# makerbot.net
KiCad netlist of a schematic drawn in EAGLE
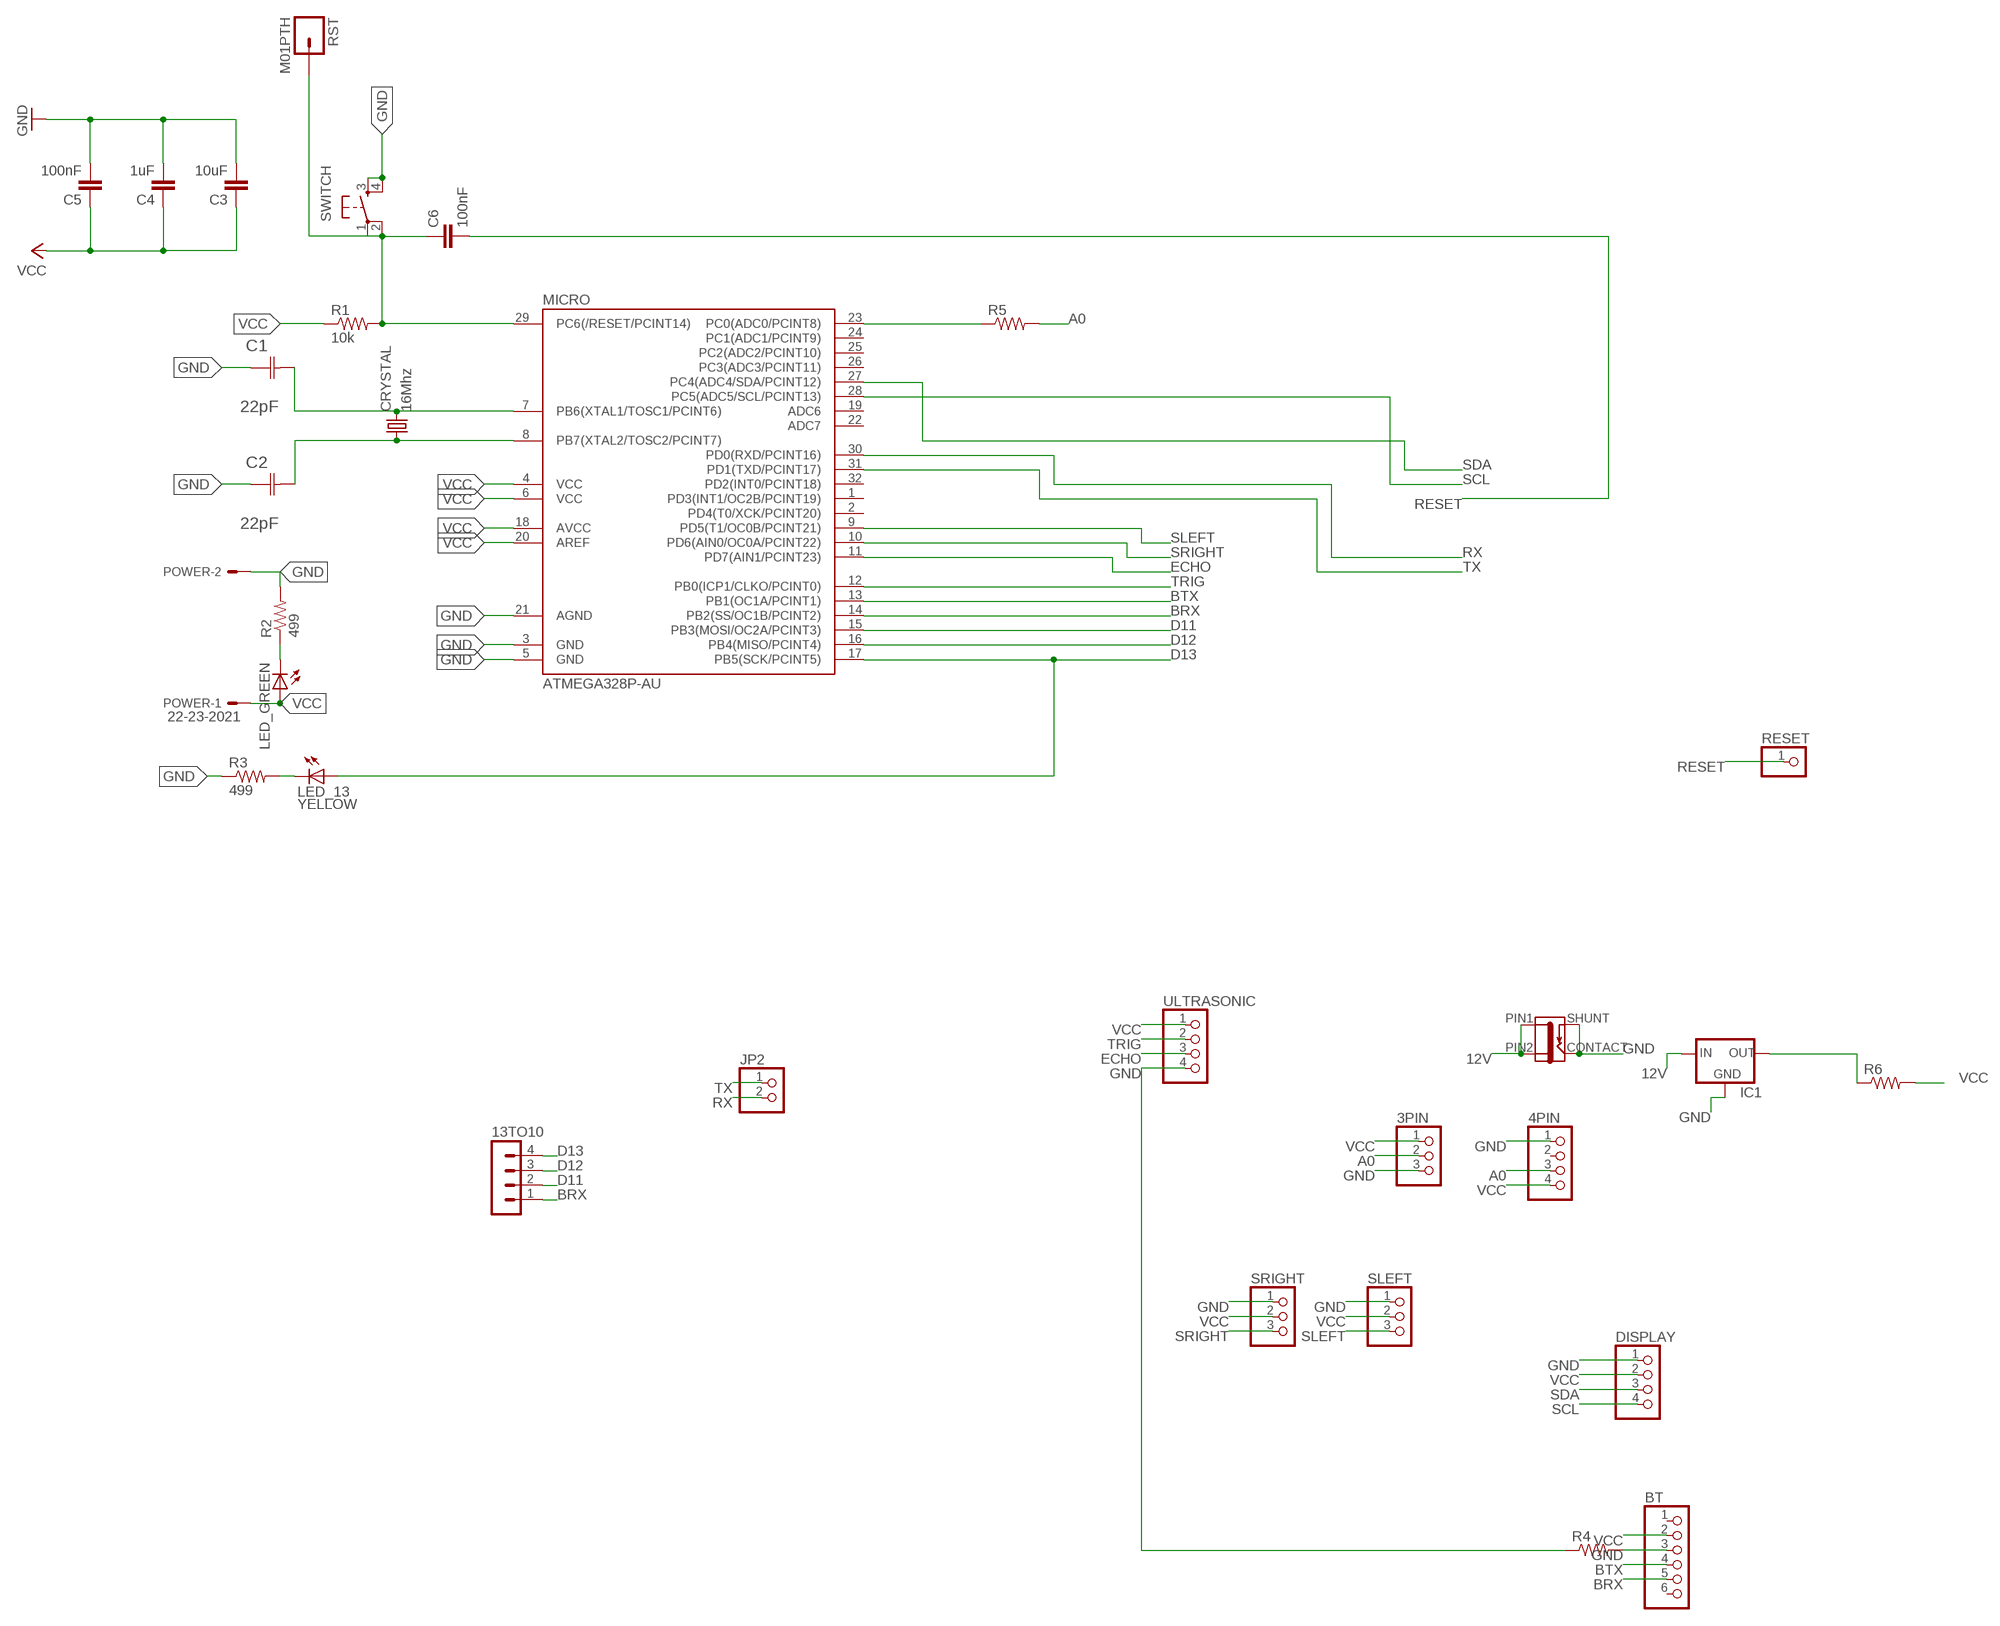
[diagram p0: schematic, sheet 1]

(export (version "E")
  (design (tool "Eeschema 10.0.6"))
  (components
    (comp (ref "3PIN")
      (value "PINHD-1X3")
      (footprint "eagle-import:1X03")
      (libsource (lib "eagle-import") (part "PINHD-1X3"))
    )
    (comp (ref "4PIN")
      (value "PINHD-1X4")
      (footprint "eagle-import:1X04")
      (libsource (lib "eagle-import") (part "PINHD-1X4"))
    )
    (comp (ref "13TO10")
      (value "MA04-1")
      (footprint "eagle-import:MA04-1")
      (libsource (lib "eagle-import") (part "MA04-1"))
    )
    (comp (ref "BT")
      (value "PINHD-1X6")
      (footprint "eagle-import:1X06")
      (libsource (lib "eagle-import") (part "PINHD-1X6"))
    )
    (comp (ref "C1")
      (value "22pF")
      (footprint "eagle-import:CAPC3216X178N")
      (fields (field (name "MPN") "0612ZC225MAT2A") (field (name "TOLERANCE") "±20%"))
      (libsource (lib "eagle-import") (part "0612ZC225MAT2A"))
    )
    (comp (ref "C2")
      (value "22pF")
      (footprint "eagle-import:CAPC3216X178N")
      (fields (field (name "MPN") "0612ZC225MAT2A") (field (name "TOLERANCE") "±20%"))
      (libsource (lib "eagle-import") (part "0612ZC225MAT2A"))
    )
    (comp (ref "C3")
      (value "10uF")
      (footprint "eagle-import:1206")
      (libsource (lib "eagle-import") (part "CAP1206"))
    )
    (comp (ref "C4")
      (value "1uF")
      (footprint "eagle-import:1206")
      (libsource (lib "eagle-import") (part "CAP1206"))
    )
    (comp (ref "C5")
      (value "100nF")
      (footprint "eagle-import:1206")
      (libsource (lib "eagle-import") (part "CAP1206"))
    )
    (comp (ref "C6")
      (value "100nF")
      (footprint "eagle-import:1206")
      (libsource (lib "eagle-import") (part "CAP1206"))
    )
    (comp (ref "CRYSTAL")
      (value "16Mhz")
      (footprint "eagle-import:CSM-7X-DU")
      (libsource (lib "eagle-import") (part "CSM-7X-DU"))
    )
    (comp (ref "DISPLAY")
      (value "PINHD-1X4")
      (footprint "eagle-import:1X04")
      (libsource (lib "eagle-import") (part "PINHD-1X4"))
    )
    (comp (ref "IC1")
      (value "78XXL")
      (footprint "eagle-import:78XXL")
      (libsource (lib "eagle-import") (part "78XXL"))
    )
    (comp (ref "J1")
      (value "JACK-2.1MM")
      (footprint "eagle-import:PJ-002AH-SMT")
      (libsource (lib "eagle-import") (part "JACK-2.1MM"))
    )
    (comp (ref "JP2")
      (value "PINHD-1X2")
      (footprint "eagle-import:1X02")
      (libsource (lib "eagle-import") (part "PINHD-1X2"))
    )
    (comp (ref "LED_13")
      (value "YELLOW")
      (footprint "eagle-import:1206")
      (libsource (lib "eagle-import") (part "LED1206"))
    )
    (comp (ref "LED_GREEN")
      (value "LED1206")
      (footprint "eagle-import:1206")
      (libsource (lib "eagle-import") (part "LED1206"))
    )
    (comp (ref "MICRO")
      (value "ATMEGA328P-AU")
      (footprint "eagle-import:TQFP32-08")
      (libsource (lib "eagle-import") (part "ATMEGA48/88/168-AU"))
    )
    (comp (ref "POWER")
      (value "22-23-2021")
      (footprint "eagle-import:22-23-2021")
      (fields (field (name "MF") "MOLEX"))
      (libsource (lib "eagle-import") (part "22-23-2021"))
    )
    (comp (ref "R1")
      (value "10k")
      (footprint "eagle-import:1206")
      (libsource (lib "eagle-import") (part "RESISTOR1206"))
    )
    (comp (ref "R2")
      (value "499")
      (footprint "eagle-import:1206")
      (libsource (lib "eagle-import") (part "RESISTOR1206"))
    )
    (comp (ref "R3")
      (value "499")
      (footprint "eagle-import:1206")
      (libsource (lib "eagle-import") (part "RESISTOR1206"))
    )
    (comp (ref "R4")
      (value "RES-US1206FAB")
      (footprint "eagle-import:R1206FAB")
      (libsource (lib "eagle-import") (part "RES-US1206FAB"))
    )
    (comp (ref "R5")
      (value "RES-US1206FAB")
      (footprint "eagle-import:R1206FAB")
      (libsource (lib "eagle-import") (part "RES-US1206FAB"))
    )
    (comp (ref "R6")
      (value "RES-US1206FAB")
      (footprint "eagle-import:R1206FAB")
      (libsource (lib "eagle-import") (part "RES-US1206FAB"))
    )
    (comp (ref "RESET")
      (value "PINHD-1X1")
      (footprint "eagle-import:1X01")
      (libsource (lib "eagle-import") (part "PINHD-1X1"))
    )
    (comp (ref "RST")
      (value "M01PTH")
      (footprint "eagle-import:1X01")
      (libsource (lib "eagle-import") (part "M01PTH"))
    )
    (comp (ref "SLEFT")
      (value "PINHD-1X3")
      (footprint "eagle-import:1X03")
      (libsource (lib "eagle-import") (part "PINHD-1X3"))
    )
    (comp (ref "SRIGHT")
      (value "PINHD-1X3")
      (footprint "eagle-import:1X03")
      (libsource (lib "eagle-import") (part "PINHD-1X3"))
    )
    (comp (ref "SWITCH")
      (value "6MM_SWITCH6MM_SWITCH")
      (footprint "eagle-import:6MM_SWITCH")
      (libsource (lib "eagle-import") (part "6MM_SWITCH6MM_SWITCH"))
    )
    (comp (ref "ULTRASONIC")
      (value "PINHD-1X4")
      (footprint "eagle-import:1X04")
      (libsource (lib "eagle-import") (part "PINHD-1X4"))
    )
  )
  (nets
    (net (code "1") (name "/12V") (class "Default")
      (node (ref "IC1") (pin "IN") (pinfunction "IN_IN") (pintype "input"))
      (node (ref "J1") (pin "PIN1") (pinfunction "PIN1_PIN1") (pintype "power_in"))
      (node (ref "J1") (pin "PIN2") (pinfunction "PIN2_PIN2") (pintype "power_in"))
    )
    (net (code "2") (name "/A0") (class "Default")
      (node (ref "3PIN") (pin "2") (pinfunction "2_2") (pintype "passive"))
      (node (ref "4PIN") (pin "3") (pinfunction "3_3") (pintype "passive"))
      (node (ref "MICRO") (pin "23") (pinfunction "PC0(ADC0/PCINT8)_23") (pintype "bidirectional"))
      (node (ref "R5") (pin "1") (pinfunction "1_1") (pintype "passive"))
      (node (ref "R5") (pin "2") (pinfunction "2_2") (pintype "passive"))
    )
    (net (code "3") (name "/BRX") (class "Default")
      (node (ref "13TO10") (pin "1") (pinfunction "1_1") (pintype "passive"))
      (node (ref "BT") (pin "5") (pinfunction "5_5") (pintype "passive"))
      (node (ref "MICRO") (pin "14") (pinfunction "PB2(SS/OC1B/PCINT2)_14") (pintype "bidirectional"))
    )
    (net (code "4") (name "/BTX") (class "Default")
      (node (ref "BT") (pin "4") (pinfunction "4_4") (pintype "passive"))
      (node (ref "MICRO") (pin "13") (pinfunction "PB1(OC1A/PCINT1)_13") (pintype "bidirectional"))
    )
    (net (code "5") (name "/D11") (class "Default")
      (node (ref "13TO10") (pin "2") (pinfunction "2_2") (pintype "passive"))
      (node (ref "MICRO") (pin "15") (pinfunction "PB3(MOSI/OC2A/PCINT3)_15") (pintype "bidirectional"))
    )
    (net (code "6") (name "/D12") (class "Default")
      (node (ref "13TO10") (pin "3") (pinfunction "3_3") (pintype "passive"))
      (node (ref "MICRO") (pin "16") (pinfunction "PB4(MISO/PCINT4)_16") (pintype "bidirectional"))
    )
    (net (code "7") (name "/D13") (class "Default")
      (node (ref "13TO10") (pin "4") (pinfunction "4_4") (pintype "passive"))
      (node (ref "LED_13") (pin "1") (pinfunction "A_1") (pintype "passive"))
      (node (ref "MICRO") (pin "17") (pinfunction "PB5(SCK/PCINT5)_17") (pintype "bidirectional"))
    )
    (net (code "8") (name "/ECHO") (class "Default")
      (node (ref "MICRO") (pin "11") (pinfunction "PD7(AIN1/PCINT23)_11") (pintype "bidirectional"))
      (node (ref "ULTRASONIC") (pin "3") (pinfunction "3_3") (pintype "passive"))
    )
    (net (code "9") (name "/RESET") (class "Default")
      (node (ref "C6") (pin "2") (pinfunction "2_2") (pintype "passive"))
      (node (ref "RESET") (pin "1") (pinfunction "1_1") (pintype "passive"))
    )
    (net (code "10") (name "/RX") (class "Default")
      (node (ref "JP2") (pin "2") (pinfunction "2_2") (pintype "passive"))
      (node (ref "MICRO") (pin "30") (pinfunction "PD0(RXD/PCINT16)_30") (pintype "bidirectional"))
    )
    (net (code "11") (name "/SCL") (class "Default")
      (node (ref "DISPLAY") (pin "4") (pinfunction "4_4") (pintype "passive"))
      (node (ref "MICRO") (pin "28") (pinfunction "PC5(ADC5/SCL/PCINT13)_28") (pintype "bidirectional"))
    )
    (net (code "12") (name "/SDA") (class "Default")
      (node (ref "DISPLAY") (pin "3") (pinfunction "3_3") (pintype "passive"))
      (node (ref "MICRO") (pin "27") (pinfunction "PC4(ADC4/SDA/PCINT12)_27") (pintype "bidirectional"))
    )
    (net (code "13") (name "/SLEFT") (class "Default")
      (node (ref "MICRO") (pin "9") (pinfunction "PD5(T1/OC0B/PCINT21)_9") (pintype "bidirectional"))
      (node (ref "SLEFT") (pin "3") (pinfunction "3_3") (pintype "passive"))
    )
    (net (code "14") (name "/SRIGHT") (class "Default")
      (node (ref "MICRO") (pin "10") (pinfunction "PD6(AIN0/OC0A/PCINT22)_10") (pintype "bidirectional"))
      (node (ref "SRIGHT") (pin "3") (pinfunction "3_3") (pintype "passive"))
    )
    (net (code "15") (name "/TRIG") (class "Default")
      (node (ref "MICRO") (pin "12") (pinfunction "PB0(ICP1/CLKO/PCINT0)_12") (pintype "bidirectional"))
      (node (ref "ULTRASONIC") (pin "2") (pinfunction "2_2") (pintype "passive"))
    )
    (net (code "16") (name "/TX") (class "Default")
      (node (ref "JP2") (pin "1") (pinfunction "1_1") (pintype "passive"))
      (node (ref "MICRO") (pin "31") (pinfunction "PD1(TXD/PCINT17)_31") (pintype "bidirectional"))
    )
    (net (code "17") (name "GND") (class "Default")
      (node (ref "3PIN") (pin "3") (pinfunction "3_3") (pintype "passive"))
      (node (ref "4PIN") (pin "1") (pinfunction "1_1") (pintype "passive"))
      (node (ref "BT") (pin "3") (pinfunction "3_3") (pintype "passive"))
      (node (ref "C1") (pin "1") (pinfunction "C1_1") (pintype "passive"))
      (node (ref "C2") (pin "1") (pinfunction "C1_1") (pintype "passive"))
      (node (ref "C3") (pin "2") (pinfunction "2_2") (pintype "passive"))
      (node (ref "C4") (pin "2") (pinfunction "2_2") (pintype "passive"))
      (node (ref "C5") (pin "2") (pinfunction "2_2") (pintype "passive"))
      (node (ref "DISPLAY") (pin "1") (pinfunction "1_1") (pintype "passive"))
      (node (ref "IC1") (pin "GND") (pinfunction "GND_GND") (pintype "input"))
      (node (ref "J1") (pin "CONTACT") (pinfunction "CONTACT_CONTACT") (pintype "power_in"))
      (node (ref "J1") (pin "SHUNT") (pinfunction "SHUNT_SHUNT") (pintype "power_in"))
      (node (ref "MICRO") (pin "21") (pinfunction "AGND_21") (pintype "power_in"))
      (node (ref "MICRO") (pin "3") (pinfunction "GND_3") (pintype "power_in"))
      (node (ref "MICRO") (pin "5") (pinfunction "GND_5") (pintype "power_in"))
      (node (ref "POWER") (pin "2") (pinfunction "S_2") (pintype "passive"))
      (node (ref "R2") (pin "2") (pinfunction "2_2") (pintype "passive"))
      (node (ref "R3") (pin "1") (pinfunction "1_1") (pintype "passive"))
      (node (ref "R4") (pin "1") (pinfunction "1_1") (pintype "passive"))
      (node (ref "R4") (pin "2") (pinfunction "2_2") (pintype "passive"))
      (node (ref "SLEFT") (pin "1") (pinfunction "1_1") (pintype "passive"))
      (node (ref "SRIGHT") (pin "1") (pinfunction "1_1") (pintype "passive"))
      (node (ref "SWITCH") (pin "3") (pinfunction "S_3") (pintype "passive"))
      (node (ref "SWITCH") (pin "4") (pinfunction "S1_4") (pintype "passive"))
      (node (ref "ULTRASONIC") (pin "4") (pinfunction "4_4") (pintype "passive"))
    )
    (net (code "18") (name "Net-(C1-C2)") (class "Default")
      (node (ref "C1") (pin "2") (pinfunction "C2_2") (pintype "passive"))
      (node (ref "CRYSTAL") (pin "2") (pinfunction "2_2") (pintype "passive"))
      (node (ref "MICRO") (pin "7") (pinfunction "PB6(XTAL1/TOSC1/PCINT6)_7") (pintype "bidirectional"))
    )
    (net (code "19") (name "Net-(C2-C2)") (class "Default")
      (node (ref "C2") (pin "2") (pinfunction "C2_2") (pintype "passive"))
      (node (ref "CRYSTAL") (pin "1") (pinfunction "1_1") (pintype "passive"))
      (node (ref "MICRO") (pin "8") (pinfunction "PB7(XTAL2/TOSC2/PCINT7)_8") (pintype "bidirectional"))
    )
    (net (code "20") (name "Net-(LED_13-C)") (class "Default")
      (node (ref "LED_13") (pin "2") (pinfunction "C_2") (pintype "passive"))
      (node (ref "R3") (pin "2") (pinfunction "2_2") (pintype "passive"))
    )
    (net (code "21") (name "Net-(LED_GREEN-C)") (class "Default")
      (node (ref "LED_GREEN") (pin "2") (pinfunction "C_2") (pintype "passive"))
      (node (ref "R2") (pin "1") (pinfunction "1_1") (pintype "passive"))
    )
    (net (code "22") (name "Net-(MICRO-PC6({slash}RESET{slash}PCINT14))") (class "Default")
      (node (ref "C6") (pin "1") (pinfunction "1_1") (pintype "passive"))
      (node (ref "MICRO") (pin "29") (pinfunction "PC6(/RESET/PCINT14)_29") (pintype "bidirectional"))
      (node (ref "R1") (pin "2") (pinfunction "2_2") (pintype "passive"))
      (node (ref "RST") (pin "1") (pinfunction "1_1") (pintype "passive"))
      (node (ref "SWITCH") (pin "1") (pinfunction "P_1") (pintype "passive"))
      (node (ref "SWITCH") (pin "2") (pinfunction "P1_2") (pintype "passive"))
    )
    (net (code "23") (name "VCC") (class "Default")
      (node (ref "3PIN") (pin "1") (pinfunction "1_1") (pintype "passive"))
      (node (ref "4PIN") (pin "4") (pinfunction "4_4") (pintype "passive"))
      (node (ref "BT") (pin "2") (pinfunction "2_2") (pintype "passive"))
      (node (ref "C3") (pin "1") (pinfunction "1_1") (pintype "passive"))
      (node (ref "C4") (pin "1") (pinfunction "1_1") (pintype "passive"))
      (node (ref "C5") (pin "1") (pinfunction "1_1") (pintype "passive"))
      (node (ref "DISPLAY") (pin "2") (pinfunction "2_2") (pintype "passive"))
      (node (ref "IC1") (pin "OUT") (pinfunction "OUT_OUT") (pintype "passive"))
      (node (ref "LED_GREEN") (pin "1") (pinfunction "A_1") (pintype "passive"))
      (node (ref "MICRO") (pin "18") (pinfunction "AVCC_18") (pintype "passive"))
      (node (ref "MICRO") (pin "20") (pinfunction "AREF_20") (pintype "passive"))
      (node (ref "MICRO") (pin "4") (pinfunction "VCC_4") (pintype "power_in"))
      (node (ref "MICRO") (pin "6") (pinfunction "VCC_6") (pintype "power_in"))
      (node (ref "POWER") (pin "1") (pinfunction "S_1") (pintype "passive"))
      (node (ref "R1") (pin "1") (pinfunction "1_1") (pintype "passive"))
      (node (ref "R6") (pin "1") (pinfunction "1_1") (pintype "passive"))
      (node (ref "R6") (pin "2") (pinfunction "2_2") (pintype "passive"))
      (node (ref "SLEFT") (pin "2") (pinfunction "2_2") (pintype "passive"))
      (node (ref "SRIGHT") (pin "2") (pinfunction "2_2") (pintype "passive"))
      (node (ref "ULTRASONIC") (pin "1") (pinfunction "1_1") (pintype "passive"))
    )
    (net (code "24") (name "unconnected-(4PIN-Pad2)") (class "Default")
      (node (ref "4PIN") (pin "2") (pinfunction "2_2") (pintype "passive"))
    )
    (net (code "25") (name "unconnected-(BT-Pad1)") (class "Default")
      (node (ref "BT") (pin "1") (pinfunction "1_1") (pintype "passive"))
    )
    (net (code "26") (name "unconnected-(BT-Pad6)") (class "Default")
      (node (ref "BT") (pin "6") (pinfunction "6_6") (pintype "passive"))
    )
    (net (code "27") (name "unconnected-(MICRO-ADC6-Pad19)") (class "Default")
      (node (ref "MICRO") (pin "19") (pinfunction "ADC6_19") (pintype "passive"))
    )
    (net (code "28") (name "unconnected-(MICRO-ADC7-Pad22)") (class "Default")
      (node (ref "MICRO") (pin "22") (pinfunction "ADC7_22") (pintype "passive"))
    )
    (net (code "29") (name "unconnected-(MICRO-PC1(ADC1{slash}PCINT9)-Pad24)") (class "Default")
      (node (ref "MICRO") (pin "24") (pinfunction "PC1(ADC1/PCINT9)_24") (pintype "bidirectional"))
    )
    (net (code "30") (name "unconnected-(MICRO-PC2(ADC2{slash}PCINT10)-Pad25)") (class "Default")
      (node (ref "MICRO") (pin "25") (pinfunction "PC2(ADC2/PCINT10)_25") (pintype "bidirectional"))
    )
    (net (code "31") (name "unconnected-(MICRO-PC3(ADC3{slash}PCINT11)-Pad26)") (class "Default")
      (node (ref "MICRO") (pin "26") (pinfunction "PC3(ADC3/PCINT11)_26") (pintype "bidirectional"))
    )
    (net (code "32") (name "unconnected-(MICRO-PD2(INT0{slash}PCINT18)-Pad32)") (class "Default")
      (node (ref "MICRO") (pin "32") (pinfunction "PD2(INT0/PCINT18)_32") (pintype "bidirectional"))
    )
    (net (code "33") (name "unconnected-(MICRO-PD3(INT1{slash}OC2B{slash}PCINT19)-Pad1)") (class "Default")
      (node (ref "MICRO") (pin "1") (pinfunction "PD3(INT1/OC2B/PCINT19)_1") (pintype "bidirectional"))
    )
    (net (code "34") (name "unconnected-(MICRO-PD4(T0{slash}XCK{slash}PCINT20)-Pad2)") (class "Default")
      (node (ref "MICRO") (pin "2") (pinfunction "PD4(T0/XCK/PCINT20)_2") (pintype "bidirectional"))
    )
  )
)
